# Power.net
KiCad netlist of a schematic drawn in Altium Designer
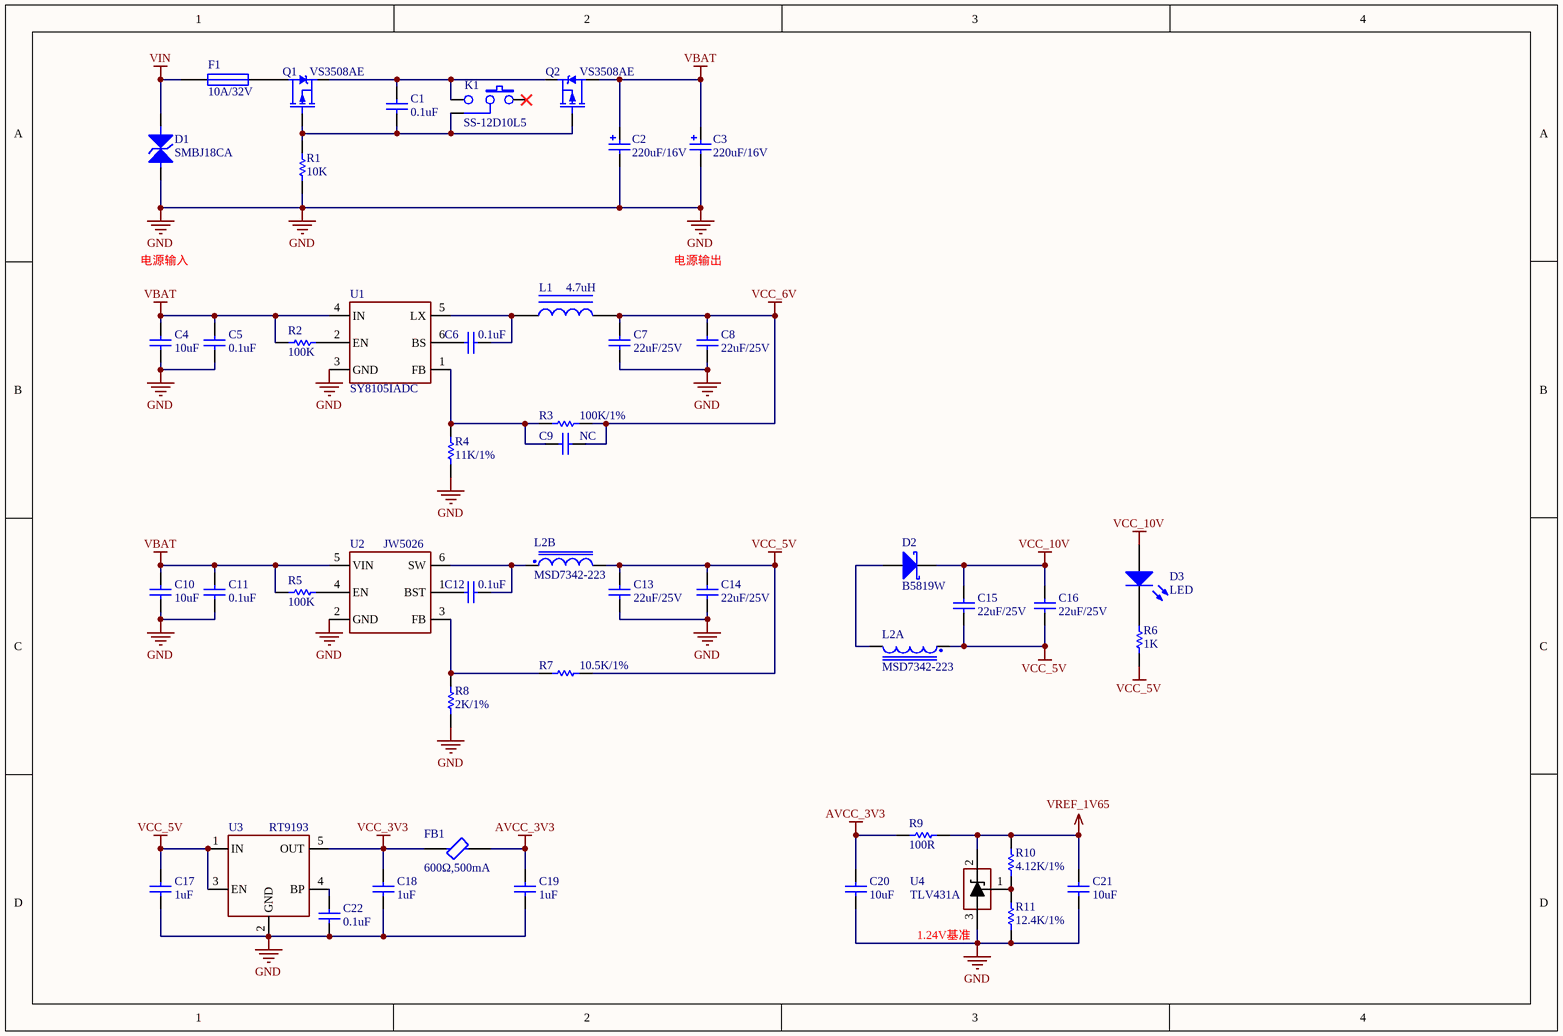
[diagram p0: Power.SchDoc]

(export (version "E")
  (design (tool "Eeschema 10.0.6"))
  (components
    (comp (ref "C1")
      (value "0.1uF")
      (footprint "C0603_NS")
      (description "Capacitor")
      (libsource (lib "Miscellaneous Devices") (part "Cap"))
    )
    (comp (ref "C2")
      (value "220uF/16V")
      (footprint "CT 2.5*6.3*7 - R")
      (description "Polarized Capacitor (Axial)")
      (fields (field (name "PUBLISHER") "Altium Limited"))
      (libsource (lib "Miscellaneous Devices") (part "Cap Pol2"))
    )
    (comp (ref "C3")
      (value "220uF/16V")
      (footprint "CT 2.5*6.3*7 - R")
      (description "Polarized Capacitor (Axial)")
      (fields (field (name "PUBLISHER") "Altium Limited"))
      (libsource (lib "Miscellaneous Devices") (part "Cap Pol2"))
    )
    (comp (ref "C4")
      (value "10uF")
      (footprint "C0603_NS")
      (description "Capacitor")
      (libsource (lib "Miscellaneous Devices") (part "Cap"))
    )
    (comp (ref "C5")
      (value "0.1uF")
      (footprint "C0603_NS")
      (description "Capacitor")
      (libsource (lib "Miscellaneous Devices") (part "Cap"))
    )
    (comp (ref "C6")
      (value "0.1uF")
      (footprint "C0603_NS")
      (description "Capacitor")
      (libsource (lib "Miscellaneous Devices") (part "Cap"))
    )
    (comp (ref "C7")
      (value "22uF/25V")
      (footprint "C0805_NS")
      (description "Capacitor")
      (libsource (lib "Miscellaneous Devices") (part "Cap"))
    )
    (comp (ref "C8")
      (value "22uF/25V")
      (footprint "C0805_NS")
      (description "Capacitor")
      (libsource (lib "Miscellaneous Devices") (part "Cap"))
    )
    (comp (ref "C9")
      (value "NC")
      (footprint "C0603_NS")
      (description "Capacitor")
      (libsource (lib "Miscellaneous Devices") (part "Cap"))
    )
    (comp (ref "C10")
      (value "10uF")
      (footprint "C0603_NS")
      (description "Capacitor")
      (libsource (lib "Miscellaneous Devices") (part "Cap"))
    )
    (comp (ref "C11")
      (value "0.1uF")
      (footprint "C0603_NS")
      (description "Capacitor")
      (libsource (lib "Miscellaneous Devices") (part "Cap"))
    )
    (comp (ref "C12")
      (value "0.1uF")
      (footprint "C0603_NS")
      (description "Capacitor")
      (libsource (lib "Miscellaneous Devices") (part "Cap"))
    )
    (comp (ref "C13")
      (value "22uF/25V")
      (footprint "C0805_NS")
      (description "Capacitor")
      (libsource (lib "Miscellaneous Devices") (part "Cap"))
    )
    (comp (ref "C14")
      (value "22uF/25V")
      (footprint "C0805_NS")
      (description "Capacitor")
      (libsource (lib "Miscellaneous Devices") (part "Cap"))
    )
    (comp (ref "C15")
      (value "22uF/25V")
      (footprint "C0805_NS")
      (description "Capacitor")
      (libsource (lib "Miscellaneous Devices") (part "Cap"))
    )
    (comp (ref "C16")
      (value "22uF/25V")
      (footprint "C0805_NS")
      (description "Capacitor")
      (libsource (lib "Miscellaneous Devices") (part "Cap"))
    )
    (comp (ref "C17")
      (value "1uF")
      (footprint "C0603_NS")
      (description "Capacitor")
      (libsource (lib "Miscellaneous Devices") (part "Cap"))
    )
    (comp (ref "C18")
      (value "1uF")
      (footprint "C0603_NS")
      (description "Capacitor")
      (libsource (lib "Miscellaneous Devices") (part "Cap"))
    )
    (comp (ref "C19")
      (value "1uF")
      (footprint "C0603_NS")
      (description "Capacitor")
      (libsource (lib "Miscellaneous Devices") (part "Cap"))
    )
    (comp (ref "C20")
      (value "10uF")
      (footprint "C0603_NS")
      (description "Capacitor")
      (libsource (lib "Miscellaneous Devices") (part "Cap"))
    )
    (comp (ref "C21")
      (value "10uF")
      (footprint "C0603_NS")
      (description "Capacitor")
      (libsource (lib "Miscellaneous Devices") (part "Cap"))
    )
    (comp (ref "C22")
      (value "0.1uF")
      (footprint "C0603_NS")
      (description "Capacitor")
      (libsource (lib "Miscellaneous Devices") (part "Cap"))
    )
    (comp (ref "D1")
      (value "SMBJ18CA")
      (footprint "1.30-二极管-整流桥堆:SMB")
      (description "双向瞬态抑制二极管")
      (libsource (lib "二极管") (part "TVS"))
    )
    (comp (ref "D2")
      (value "B5819W")
      (footprint "SOD-123")
      (description "Schottky Diode")
      (fields (field (name "PUBLISHER") "Altium Limited"))
      (libsource (lib "my_library") (part "D Schottky"))
    )
    (comp (ref "D3")
      (value "LED")
      (footprint "LED0603_NS")
      (description "Typical INFRARED GaAs LED")
      (libsource (lib "Miscellaneous Devices") (part "LED0"))
    )
    (comp (ref "F1")
      (value "10A/32V")
      (footprint "FU 1206")
      (description "Fuse")
      (fields (field (name "PUBLISHER") "Altium Limited"))
      (libsource (lib "Miscellaneous Devices") (part "Fuse 1"))
    )
    (comp (ref "FB1")
      (value "600Ω,500mA")
      (footprint "FB0603_NS")
      (libsource (lib "my_library") (part "Ferrite Bead"))
    )
    (comp (ref "K1") (value "SS-12D10L5") (footprint "SS-12D10") (libsource (lib "MySchLib") (part "SW2")))
    (comp (ref "L1")
      (value "4.7uH")
      (footprint "L-SMD-0630")
      (description "Magnetic-Core Inductor")
      (libsource (lib "Miscellaneous Devices") (part "Inductor Iron"))
    )
    (comp (ref "L2")
      (value "MSD7342-223")
      (footprint "MSD7342")
      (libsource (lib "") (part "Coupled Inductor_1"))
    )
    (comp (ref "Q1")
      (value "VS3508AE")
      (footprint "PowerPAK1212-8")
      (description "P沟道场效应管")
      (libsource (lib "my_library") (part "P-MOS"))
    )
    (comp (ref "Q2")
      (value "VS3508AE")
      (footprint "PowerPAK1212-8")
      (description "P沟道场效应管")
      (libsource (lib "my_library") (part "P-MOS"))
    )
    (comp (ref "R1")
      (value "10K")
      (footprint "R0603_NS")
      (description "Resistor")
      (libsource (lib "Miscellaneous Devices") (part "Res1"))
    )
    (comp (ref "R2")
      (value "100K")
      (footprint "R0603_NS")
      (description "Resistor")
      (libsource (lib "Miscellaneous Devices") (part "Res1"))
    )
    (comp (ref "R3")
      (value "100K/1%")
      (footprint "R0603_NS")
      (description "Resistor")
      (libsource (lib "Miscellaneous Devices") (part "Res1"))
    )
    (comp (ref "R4")
      (value "11K/1%")
      (footprint "R0603_NS")
      (description "Resistor")
      (libsource (lib "Miscellaneous Devices") (part "Res1"))
    )
    (comp (ref "R5")
      (value "100K")
      (footprint "R0603_NS")
      (description "Resistor")
      (libsource (lib "Miscellaneous Devices") (part "Res1"))
    )
    (comp (ref "R6")
      (value "1K")
      (footprint "R0603_NS")
      (description "Resistor")
      (libsource (lib "Miscellaneous Devices") (part "Res1"))
    )
    (comp (ref "R7")
      (value "10.5K/1%")
      (footprint "R0603_NS")
      (description "Resistor")
      (libsource (lib "Miscellaneous Devices") (part "Res1"))
    )
    (comp (ref "R8")
      (value "2K/1%")
      (footprint "R0603_NS")
      (description "Resistor")
      (libsource (lib "Miscellaneous Devices") (part "Res1"))
    )
    (comp (ref "R9")
      (value "100R")
      (footprint "R0603_NS")
      (description "Resistor")
      (libsource (lib "Miscellaneous Devices") (part "Res1"))
    )
    (comp (ref "R10")
      (value "4.12K/1%")
      (footprint "R0603_NS")
      (description "Resistor")
      (libsource (lib "Miscellaneous Devices") (part "Res1"))
    )
    (comp (ref "R11")
      (value "12.4K/1%")
      (footprint "R0603_NS")
      (description "Resistor")
      (libsource (lib "Miscellaneous Devices") (part "Res1"))
    )
    (comp (ref "U1")
      (value "SY8105IADC")
      (footprint "SOT23-6N")
      (libsource (lib "my_library") (part "SY8105"))
    )
    (comp (ref "U2") (value "JW5026") (footprint "SOT23-6N") (libsource (lib "my_library") (part "JW5026")))
    (comp (ref "U3") (value "RT9193") (footprint "SOT23-5N") (libsource (lib "my_library") (part "RT9193")))
    (comp (ref "U4")
      (value "TLV431A")
      (footprint "SOT23-3N")
      (libsource (lib "my_library") (part "TLV431DBZ"))
    )
  )
  (nets
    (net (code "1") (name "AVCC_3V3") (class "Default")
      (node (ref "C19") (pin "2") (pinfunction "2_2") (pintype "passive"))
      (node (ref "C20") (pin "2") (pinfunction "2_2") (pintype "passive"))
      (node (ref "FB1") (pin "2") (pinfunction "2_2") (pintype "passive"))
      (node (ref "R9") (pin "2") (pinfunction "2_2") (pintype "passive"))
    )
    (net (code "2") (name "GND") (class "Default")
      (node (ref "C10") (pin "1") (pinfunction "1_1") (pintype "passive"))
      (node (ref "C11") (pin "1") (pinfunction "1_1") (pintype "passive"))
      (node (ref "C13") (pin "1") (pinfunction "1_1") (pintype "passive"))
      (node (ref "C14") (pin "1") (pinfunction "1_1") (pintype "passive"))
      (node (ref "C17") (pin "1") (pinfunction "1_1") (pintype "passive"))
      (node (ref "C18") (pin "1") (pinfunction "1_1") (pintype "passive"))
      (node (ref "C19") (pin "1") (pinfunction "1_1") (pintype "passive"))
      (node (ref "C2") (pin "2") (pinfunction "2_2") (pintype "passive"))
      (node (ref "C20") (pin "1") (pinfunction "1_1") (pintype "passive"))
      (node (ref "C21") (pin "1") (pinfunction "1_1") (pintype "passive"))
      (node (ref "C22") (pin "1") (pinfunction "1_1") (pintype "passive"))
      (node (ref "C3") (pin "2") (pinfunction "2_2") (pintype "passive"))
      (node (ref "C4") (pin "1") (pinfunction "1_1") (pintype "passive"))
      (node (ref "C5") (pin "1") (pinfunction "1_1") (pintype "passive"))
      (node (ref "C7") (pin "1") (pinfunction "1_1") (pintype "passive"))
      (node (ref "C8") (pin "1") (pinfunction "1_1") (pintype "passive"))
      (node (ref "D1") (pin "A") (pinfunction "A_A") (pintype "passive"))
      (node (ref "R1") (pin "2") (pinfunction "2_2") (pintype "passive"))
      (node (ref "R11") (pin "1") (pinfunction "1_1") (pintype "passive"))
      (node (ref "R4") (pin "2") (pinfunction "2_2") (pintype "passive"))
      (node (ref "R8") (pin "2") (pinfunction "2_2") (pintype "passive"))
      (node (ref "U1") (pin "3") (pinfunction "GND_3") (pintype "passive"))
      (node (ref "U2") (pin "2") (pinfunction "GND_2") (pintype "passive"))
      (node (ref "U3") (pin "2") (pinfunction "GND_2") (pintype "passive"))
      (node (ref "U4") (pin "3") (pinfunction "ANODE_3") (pintype "passive"))
    )
    (net (code "3") (name "Net-(C1-Pad1)") (class "Default")
      (node (ref "C1") (pin "1") (pinfunction "1_1") (pintype "passive"))
      (node (ref "K1") (pin "2") (pinfunction "2_2") (pintype "passive"))
      (node (ref "Q1") (pin "S") (pinfunction "S_S") (pintype "passive"))
      (node (ref "Q2") (pin "S") (pinfunction "S_S") (pintype "passive"))
    )
    (net (code "4") (name "Net-(C1-Pad2)") (class "Default")
      (node (ref "C1") (pin "2") (pinfunction "2_2") (pintype "passive"))
      (node (ref "K1") (pin "1") (pinfunction "1_1") (pintype "passive"))
      (node (ref "Q1") (pin "G") (pinfunction "G_G") (pintype "passive"))
      (node (ref "Q2") (pin "G") (pinfunction "G_G") (pintype "passive"))
      (node (ref "R1") (pin "1") (pinfunction "1_1") (pintype "passive"))
    )
    (net (code "5") (name "Net-(D2-A)") (class "Default")
      (node (ref "D2") (pin "1") (pinfunction "A_1") (pintype "passive"))
      (node (ref "L2") (pin "3") (pinfunction "3_3") (pintype "passive"))
    )
    (net (code "6") (name "Net-(D3-K)") (class "Default")
      (node (ref "D3") (pin "2") (pinfunction "K_2") (pintype "passive"))
      (node (ref "R6") (pin "1") (pinfunction "1_1") (pintype "passive"))
    )
    (net (code "7") (name "Net-(F1-Pad2)") (class "Default")
      (node (ref "F1") (pin "2") (pinfunction "2_2") (pintype "passive"))
      (node (ref "Q1") (pin "D") (pinfunction "D_D") (pintype "passive"))
    )
    (net (code "8") (name "Net-(U1-BS)") (class "Default")
      (node (ref "C6") (pin "1") (pinfunction "1_1") (pintype "passive"))
      (node (ref "U1") (pin "6") (pinfunction "BS_6") (pintype "passive"))
    )
    (net (code "9") (name "Net-(U1-EN)") (class "Default")
      (node (ref "R2") (pin "1") (pinfunction "1_1") (pintype "passive"))
      (node (ref "U1") (pin "2") (pinfunction "EN_2") (pintype "passive"))
    )
    (net (code "10") (name "Net-(U1-FB)") (class "Default")
      (node (ref "C9") (pin "1") (pinfunction "1_1") (pintype "passive"))
      (node (ref "R3") (pin "1") (pinfunction "1_1") (pintype "passive"))
      (node (ref "R4") (pin "1") (pinfunction "1_1") (pintype "passive"))
      (node (ref "U1") (pin "1") (pinfunction "FB_1") (pintype "passive"))
    )
    (net (code "11") (name "Net-(U1-LX)") (class "Default")
      (node (ref "C6") (pin "2") (pinfunction "2_2") (pintype "passive"))
      (node (ref "L1") (pin "1") (pinfunction "1_1") (pintype "passive"))
      (node (ref "U1") (pin "5") (pinfunction "LX_5") (pintype "passive"))
    )
    (net (code "12") (name "Net-(U2-BST)") (class "Default")
      (node (ref "C12") (pin "1") (pinfunction "1_1") (pintype "passive"))
      (node (ref "U2") (pin "1") (pinfunction "BST_1") (pintype "passive"))
    )
    (net (code "13") (name "Net-(U2-EN)") (class "Default")
      (node (ref "R5") (pin "1") (pinfunction "1_1") (pintype "passive"))
      (node (ref "U2") (pin "4") (pinfunction "EN_4") (pintype "passive"))
    )
    (net (code "14") (name "Net-(U2-FB)") (class "Default")
      (node (ref "R7") (pin "1") (pinfunction "1_1") (pintype "passive"))
      (node (ref "R8") (pin "1") (pinfunction "1_1") (pintype "passive"))
      (node (ref "U2") (pin "3") (pinfunction "FB_3") (pintype "passive"))
    )
    (net (code "15") (name "Net-(U2-SW)") (class "Default")
      (node (ref "C12") (pin "2") (pinfunction "2_2") (pintype "passive"))
      (node (ref "L2") (pin "2") (pinfunction "2_2") (pintype "passive"))
      (node (ref "U2") (pin "6") (pinfunction "SW_6") (pintype "passive"))
    )
    (net (code "16") (name "Net-(U3-BP)") (class "Default")
      (node (ref "C22") (pin "2") (pinfunction "2_2") (pintype "passive"))
      (node (ref "U3") (pin "4") (pinfunction "BP_4") (pintype "passive"))
    )
    (net (code "17") (name "Net-(U4-REF)") (class "Default")
      (node (ref "R10") (pin "2") (pinfunction "2_2") (pintype "passive"))
      (node (ref "R11") (pin "2") (pinfunction "2_2") (pintype "passive"))
      (node (ref "U4") (pin "1") (pinfunction "REF_1") (pintype "passive"))
    )
    (net (code "18") (name "VBAT") (class "Default")
      (node (ref "C10") (pin "2") (pinfunction "2_2") (pintype "passive"))
      (node (ref "C11") (pin "2") (pinfunction "2_2") (pintype "passive"))
      (node (ref "C2") (pin "1") (pinfunction "1_1") (pintype "passive"))
      (node (ref "C3") (pin "1") (pinfunction "1_1") (pintype "passive"))
      (node (ref "C4") (pin "2") (pinfunction "2_2") (pintype "passive"))
      (node (ref "C5") (pin "2") (pinfunction "2_2") (pintype "passive"))
      (node (ref "Q2") (pin "D") (pinfunction "D_D") (pintype "passive"))
      (node (ref "R2") (pin "2") (pinfunction "2_2") (pintype "passive"))
      (node (ref "R5") (pin "2") (pinfunction "2_2") (pintype "passive"))
      (node (ref "U1") (pin "4") (pinfunction "IN_4") (pintype "passive"))
      (node (ref "U2") (pin "5") (pinfunction "VIN_5") (pintype "passive"))
    )
    (net (code "19") (name "VCC_3V3") (class "Default")
      (node (ref "C18") (pin "2") (pinfunction "2_2") (pintype "passive"))
      (node (ref "FB1") (pin "1") (pinfunction "1_1") (pintype "passive"))
      (node (ref "U3") (pin "5") (pinfunction "OUT_5") (pintype "passive"))
    )
    (net (code "20") (name "VCC_5V") (class "Default")
      (node (ref "C13") (pin "2") (pinfunction "2_2") (pintype "passive"))
      (node (ref "C14") (pin "2") (pinfunction "2_2") (pintype "passive"))
      (node (ref "C15") (pin "1") (pinfunction "1_1") (pintype "passive"))
      (node (ref "C16") (pin "1") (pinfunction "1_1") (pintype "passive"))
      (node (ref "C17") (pin "2") (pinfunction "2_2") (pintype "passive"))
      (node (ref "L2") (pin "1") (pinfunction "1_1") (pintype "passive"))
      (node (ref "L2") (pin "4") (pinfunction "4_4") (pintype "passive"))
      (node (ref "R6") (pin "2") (pinfunction "2_2") (pintype "passive"))
      (node (ref "R7") (pin "2") (pinfunction "2_2") (pintype "passive"))
      (node (ref "U3") (pin "1") (pinfunction "IN_1") (pintype "passive"))
      (node (ref "U3") (pin "3") (pinfunction "EN_3") (pintype "passive"))
    )
    (net (code "21") (name "VCC_6V") (class "Default")
      (node (ref "C7") (pin "2") (pinfunction "2_2") (pintype "passive"))
      (node (ref "C8") (pin "2") (pinfunction "2_2") (pintype "passive"))
      (node (ref "C9") (pin "2") (pinfunction "2_2") (pintype "passive"))
      (node (ref "L1") (pin "2") (pinfunction "2_2") (pintype "passive"))
      (node (ref "R3") (pin "2") (pinfunction "2_2") (pintype "passive"))
    )
    (net (code "22") (name "VCC_10V") (class "Default")
      (node (ref "C15") (pin "2") (pinfunction "2_2") (pintype "passive"))
      (node (ref "C16") (pin "2") (pinfunction "2_2") (pintype "passive"))
      (node (ref "D2") (pin "2") (pinfunction "K_2") (pintype "passive"))
      (node (ref "D3") (pin "1") (pinfunction "A_1") (pintype "passive"))
    )
    (net (code "23") (name "VIN") (class "Default")
      (node (ref "D1") (pin "K") (pinfunction "K_K") (pintype "passive"))
      (node (ref "F1") (pin "1") (pinfunction "1_1") (pintype "passive"))
    )
    (net (code "24") (name "VREF_1V65") (class "Default")
      (node (ref "C21") (pin "2") (pinfunction "2_2") (pintype "passive"))
      (node (ref "R10") (pin "1") (pinfunction "1_1") (pintype "passive"))
      (node (ref "R9") (pin "1") (pinfunction "1_1") (pintype "passive"))
      (node (ref "U4") (pin "2") (pinfunction "CATHODE_2") (pintype "passive"))
    )
    (net (code "25") (name "unconnected-(K1-Pad3)") (class "Default")
      (node (ref "K1") (pin "3") (pinfunction "3_3") (pintype "passive+no_connect"))
    )
  )
)
